# TurquoiseBicuspid.net
KiCad netlist of a schematic drawn in EAGLE
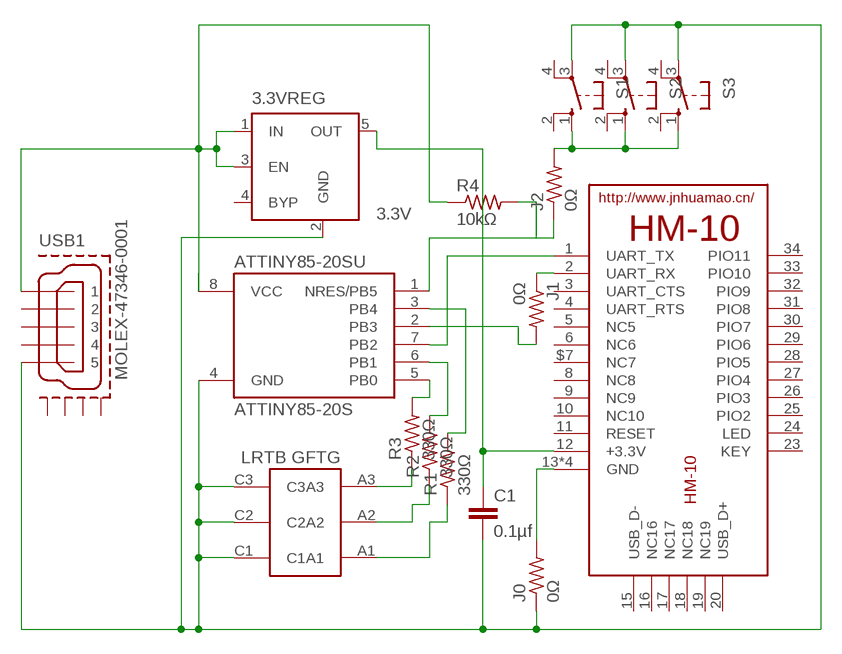
[diagram p0: schematic, sheet 1]

(export (version "E")
  (design (tool "Eeschema 10.0.6"))
  (components
    (comp (ref "3.3VREG")
      (value "3.3V")
      (footprint "eagle-import:SOT23-5")
      (libsource (lib "eagle-import") (part "MIC5219XX"))
    )
    (comp (ref "ATTINY85-20SU")
      (value "ATTINY85-20S")
      (footprint "eagle-import:SOIC8_EIAJ_208MIL")
      (libsource (lib "eagle-import") (part "ATTINY85S-20"))
    )
    (comp (ref "C1")
      (value "0.1µf")
      (footprint "eagle-import:C1206")
      (libsource (lib "eagle-import") (part "C-EUC1206"))
    )
    (comp (ref "HM-10")
      (value "HM-10-BOARD")
      (footprint "eagle-import:26.9X13X2.2_BOARD")
      (libsource (lib "eagle-import") (part "HM-10-BOARD"))
    )
    (comp (ref "J0")
      (value "0Ω")
      (footprint "eagle-import:R1206")
      (libsource (lib "eagle-import") (part "R-US_R1206"))
    )
    (comp (ref "J1")
      (value "0Ω")
      (footprint "eagle-import:R1206")
      (libsource (lib "eagle-import") (part "R-US_R1206"))
    )
    (comp (ref "J2")
      (value "0Ω")
      (footprint "eagle-import:R1206")
      (libsource (lib "eagle-import") (part "R-US_R1206"))
    )
    (comp (ref "R1")
      (value "330Ω")
      (footprint "eagle-import:M1206")
      (libsource (lib "eagle-import") (part "R-US_M1206"))
    )
    (comp (ref "R2")
      (value "330Ω")
      (footprint "eagle-import:M1206")
      (libsource (lib "eagle-import") (part "R-US_M1206"))
    )
    (comp (ref "R3")
      (value "330Ω")
      (footprint "eagle-import:M1206")
      (libsource (lib "eagle-import") (part "R-US_M1206"))
    )
    (comp (ref "R4")
      (value "10kΩ")
      (footprint "eagle-import:R1206")
      (libsource (lib "eagle-import") (part "R-US_R1206"))
    )
    (comp (ref "S1")
      (value "10-XX")
      (footprint "eagle-import:B3F-10XX")
      (fields (field (name "MPN") "B3F-1000"))
      (libsource (lib "eagle-import") (part "10-XX"))
    )
    (comp (ref "S2")
      (value "10-XX")
      (footprint "eagle-import:B3F-10XX")
      (fields (field (name "MPN") "B3F-1000"))
      (libsource (lib "eagle-import") (part "10-XX"))
    )
    (comp (ref "S3")
      (value "10-XX")
      (footprint "eagle-import:B3F-10XX")
      (fields (field (name "MPN") "B3F-1000"))
      (libsource (lib "eagle-import") (part "10-XX"))
    )
    (comp (ref "U$1")
      (value "LRTB_GFTG")
      (footprint "eagle-import:LRTB_GFTG")
      (libsource (lib "eagle-import") (part "LRTB_GFTG"))
    )
    (comp (ref "USB1")
      (value "MOLEX-47346-0001")
      (footprint "eagle-import:MOLEX-47364-0001")
      (libsource (lib "eagle-import") (part "MOLEX-47346-0001"))
    )
  )
  (nets
    (net (code "1") (name "/5V") (class "Default")
      (node (ref "3.3VREG") (pin "1") (pinfunction "IN_1") (pintype "input"))
      (node (ref "3.3VREG") (pin "3") (pinfunction "EN_3") (pintype "input"))
      (node (ref "ATTINY85-20SU") (pin "8") (pinfunction "VCC_8") (pintype "power_in"))
      (node (ref "R4") (pin "1") (pinfunction "1_1") (pintype "passive"))
      (node (ref "USB1") (pin "1") (pinfunction "1_1") (pintype "input"))
    )
    (net (code "2") (name "/A1") (class "Default")
      (node (ref "ATTINY85-20SU") (pin "3") (pinfunction "PB4_3") (pintype "bidirectional"))
      (node (ref "R1") (pin "1") (pinfunction "1_1") (pintype "passive"))
      (node (ref "R1") (pin "2") (pinfunction "2_2") (pintype "passive"))
      (node (ref "U$1") (pin "A1") (pinfunction "A1_A1") (pintype "bidirectional"))
    )
    (net (code "3") (name "/A2") (class "Default")
      (node (ref "ATTINY85-20SU") (pin "6") (pinfunction "PB1_6") (pintype "bidirectional"))
      (node (ref "R2") (pin "1") (pinfunction "1_1") (pintype "passive"))
      (node (ref "R2") (pin "2") (pinfunction "2_2") (pintype "passive"))
      (node (ref "U$1") (pin "A2") (pinfunction "A2_A2") (pintype "bidirectional"))
    )
    (net (code "4") (name "/A3") (class "Default")
      (node (ref "ATTINY85-20SU") (pin "5") (pinfunction "PB0_5") (pintype "bidirectional"))
      (node (ref "R3") (pin "1") (pinfunction "1_1") (pintype "passive"))
      (node (ref "R3") (pin "2") (pinfunction "2_2") (pintype "passive"))
      (node (ref "U$1") (pin "A3") (pinfunction "A3_A3") (pintype "bidirectional"))
    )
    (net (code "5") (name "/BT_RX") (class "Default")
      (node (ref "ATTINY85-20SU") (pin "2") (pinfunction "PB3_2") (pintype "bidirectional"))
      (node (ref "HM-10") (pin "2") (pinfunction "UART_RX_2") (pintype "bidirectional"))
      (node (ref "J1") (pin "1") (pinfunction "1_1") (pintype "passive"))
      (node (ref "J1") (pin "2") (pinfunction "2_2") (pintype "passive"))
    )
    (net (code "6") (name "/RESET") (class "Default")
      (node (ref "ATTINY85-20SU") (pin "1") (pinfunction "NRES/PB5_1") (pintype "bidirectional"))
      (node (ref "J2") (pin "1") (pinfunction "1_1") (pintype "passive"))
      (node (ref "J2") (pin "2") (pinfunction "2_2") (pintype "passive"))
      (node (ref "R4") (pin "2") (pinfunction "2_2") (pintype "passive"))
      (node (ref "S1") (pin "1") (pinfunction "S_1") (pintype "passive"))
      (node (ref "S2") (pin "1") (pinfunction "S_1") (pintype "passive"))
      (node (ref "S3") (pin "1") (pinfunction "S_1") (pintype "passive"))
    )
    (net (code "7") (name "Net-(3.3VREG-GND)") (class "Default")
      (node (ref "3.3VREG") (pin "2") (pinfunction "GND_2") (pintype "power_in"))
      (node (ref "ATTINY85-20SU") (pin "4") (pinfunction "GND_4") (pintype "power_in"))
      (node (ref "C1") (pin "2") (pinfunction "2_2") (pintype "passive"))
      (node (ref "J0") (pin "1") (pinfunction "1_1") (pintype "passive"))
      (node (ref "S1") (pin "3") (pinfunction "P_3") (pintype "passive"))
      (node (ref "S2") (pin "3") (pinfunction "P_3") (pintype "passive"))
      (node (ref "S3") (pin "3") (pinfunction "P_3") (pintype "passive"))
      (node (ref "U$1") (pin "C1") (pinfunction "C1_C1") (pintype "bidirectional"))
      (node (ref "U$1") (pin "C2") (pinfunction "C2_C2") (pintype "bidirectional"))
      (node (ref "U$1") (pin "C3") (pinfunction "C3_C3") (pintype "bidirectional"))
      (node (ref "USB1") (pin "5") (pinfunction "5_5") (pintype "input"))
    )
    (net (code "8") (name "Net-(3.3VREG-OUT)") (class "Default")
      (node (ref "3.3VREG") (pin "5") (pinfunction "OUT_5") (pintype "output"))
      (node (ref "C1") (pin "1") (pinfunction "1_1") (pintype "passive"))
      (node (ref "HM-10") (pin "12") (pinfunction "+3.3V_12") (pintype "bidirectional"))
    )
    (net (code "9") (name "Net-(ATTINY85-20SU-PB2)") (class "Default")
      (node (ref "ATTINY85-20SU") (pin "7") (pinfunction "PB2_7") (pintype "bidirectional"))
      (node (ref "HM-10") (pin "1") (pinfunction "UART_TX_1") (pintype "bidirectional"))
    )
    (net (code "10") (name "Net-(HM-10-GND-Pad13)") (class "Default")
      (node (ref "HM-10") (pin "13") (pinfunction "GND_13") (pintype "bidirectional"))
      (node (ref "HM-10") (pin "14") (pinfunction "GND_14") (pintype "bidirectional"))
      (node (ref "HM-10") (pin "21") (pinfunction "GND_21") (pintype "bidirectional"))
      (node (ref "HM-10") (pin "22") (pinfunction "GND_22") (pintype "bidirectional"))
      (node (ref "J0") (pin "2") (pinfunction "2_2") (pintype "passive"))
    )
    (net (code "11") (name "unconnected-(3.3VREG-BYP-Pad4)") (class "Default")
      (node (ref "3.3VREG") (pin "4") (pinfunction "BYP_4") (pintype "passive"))
    )
    (net (code "12") (name "unconnected-(HM-10-KEY-Pad23)") (class "Default")
      (node (ref "HM-10") (pin "23") (pinfunction "KEY_23") (pintype "bidirectional"))
    )
    (net (code "13") (name "unconnected-(HM-10-LED-Pad24)") (class "Default")
      (node (ref "HM-10") (pin "24") (pinfunction "LED_24") (pintype "bidirectional"))
    )
    (net (code "14") (name "unconnected-(HM-10-NC5-Pad5)") (class "Default")
      (node (ref "HM-10") (pin "5") (pinfunction "NC5_5") (pintype "bidirectional"))
    )
    (net (code "15") (name "unconnected-(HM-10-NC6-Pad6)") (class "Default")
      (node (ref "HM-10") (pin "6") (pinfunction "NC6_6") (pintype "bidirectional"))
    )
    (net (code "16") (name "unconnected-(HM-10-NC7-Pad$7)") (class "Default")
      (node (ref "HM-10") (pin "$7") (pinfunction "NC7_$7") (pintype "bidirectional"))
    )
    (net (code "17") (name "unconnected-(HM-10-NC8-Pad8)") (class "Default")
      (node (ref "HM-10") (pin "8") (pinfunction "NC8_8") (pintype "bidirectional"))
    )
    (net (code "18") (name "unconnected-(HM-10-NC9-Pad9)") (class "Default")
      (node (ref "HM-10") (pin "9") (pinfunction "NC9_9") (pintype "bidirectional"))
    )
    (net (code "19") (name "unconnected-(HM-10-NC10-Pad10)") (class "Default")
      (node (ref "HM-10") (pin "10") (pinfunction "NC10_10") (pintype "bidirectional"))
    )
    (net (code "20") (name "unconnected-(HM-10-NC16-Pad16)") (class "Default")
      (node (ref "HM-10") (pin "16") (pinfunction "NC16_16") (pintype "bidirectional"))
    )
    (net (code "21") (name "unconnected-(HM-10-NC17-Pad17)") (class "Default")
      (node (ref "HM-10") (pin "17") (pinfunction "NC17_17") (pintype "bidirectional"))
    )
    (net (code "22") (name "unconnected-(HM-10-NC18-Pad18)") (class "Default")
      (node (ref "HM-10") (pin "18") (pinfunction "NC18_18") (pintype "bidirectional"))
    )
    (net (code "23") (name "unconnected-(HM-10-NC19-Pad19)") (class "Default")
      (node (ref "HM-10") (pin "19") (pinfunction "NC19_19") (pintype "bidirectional"))
    )
    (net (code "24") (name "unconnected-(HM-10-PIO2-Pad25)") (class "Default")
      (node (ref "HM-10") (pin "25") (pinfunction "PIO2_25") (pintype "bidirectional"))
    )
    (net (code "25") (name "unconnected-(HM-10-PIO3-Pad26)") (class "Default")
      (node (ref "HM-10") (pin "26") (pinfunction "PIO3_26") (pintype "bidirectional"))
    )
    (net (code "26") (name "unconnected-(HM-10-PIO4-Pad27)") (class "Default")
      (node (ref "HM-10") (pin "27") (pinfunction "PIO4_27") (pintype "bidirectional"))
    )
    (net (code "27") (name "unconnected-(HM-10-PIO5-Pad28)") (class "Default")
      (node (ref "HM-10") (pin "28") (pinfunction "PIO5_28") (pintype "bidirectional"))
    )
    (net (code "28") (name "unconnected-(HM-10-PIO6-Pad29)") (class "Default")
      (node (ref "HM-10") (pin "29") (pinfunction "PIO6_29") (pintype "bidirectional"))
    )
    (net (code "29") (name "unconnected-(HM-10-PIO7-Pad30)") (class "Default")
      (node (ref "HM-10") (pin "30") (pinfunction "PIO7_30") (pintype "bidirectional"))
    )
    (net (code "30") (name "unconnected-(HM-10-PIO8-Pad31)") (class "Default")
      (node (ref "HM-10") (pin "31") (pinfunction "PIO8_31") (pintype "bidirectional"))
    )
    (net (code "31") (name "unconnected-(HM-10-PIO9-Pad32)") (class "Default")
      (node (ref "HM-10") (pin "32") (pinfunction "PIO9_32") (pintype "bidirectional"))
    )
    (net (code "32") (name "unconnected-(HM-10-PIO10-Pad33)") (class "Default")
      (node (ref "HM-10") (pin "33") (pinfunction "PIO10_33") (pintype "bidirectional"))
    )
    (net (code "33") (name "unconnected-(HM-10-PIO11-Pad34)") (class "Default")
      (node (ref "HM-10") (pin "34") (pinfunction "PIO11_34") (pintype "bidirectional"))
    )
    (net (code "34") (name "unconnected-(HM-10-RESET-Pad11)") (class "Default")
      (node (ref "HM-10") (pin "11") (pinfunction "RESET_11") (pintype "bidirectional"))
    )
    (net (code "35") (name "unconnected-(HM-10-UART_CTS-Pad3)") (class "Default")
      (node (ref "HM-10") (pin "3") (pinfunction "UART_CTS_3") (pintype "bidirectional"))
    )
    (net (code "36") (name "unconnected-(HM-10-UART_RTS-Pad4)") (class "Default")
      (node (ref "HM-10") (pin "4") (pinfunction "UART_RTS_4") (pintype "bidirectional"))
    )
    (net (code "37") (name "unconnected-(HM-10-USB_D+-Pad20)") (class "Default")
      (node (ref "HM-10") (pin "20") (pinfunction "USB_D+_20") (pintype "bidirectional"))
    )
    (net (code "38") (name "unconnected-(HM-10-USB_D--Pad15)") (class "Default")
      (node (ref "HM-10") (pin "15") (pinfunction "USB_D-_15") (pintype "bidirectional"))
    )
    (net (code "39") (name "unconnected-(S1-P1-Pad4)") (class "Default")
      (node (ref "S1") (pin "4") (pinfunction "P1_4") (pintype "passive"))
    )
    (net (code "40") (name "unconnected-(S1-S1-Pad2)") (class "Default")
      (node (ref "S1") (pin "2") (pinfunction "S1_2") (pintype "passive"))
    )
    (net (code "41") (name "unconnected-(S2-P1-Pad4)") (class "Default")
      (node (ref "S2") (pin "4") (pinfunction "P1_4") (pintype "passive"))
    )
    (net (code "42") (name "unconnected-(S2-S1-Pad2)") (class "Default")
      (node (ref "S2") (pin "2") (pinfunction "S1_2") (pintype "passive"))
    )
    (net (code "43") (name "unconnected-(S3-P1-Pad4)") (class "Default")
      (node (ref "S3") (pin "4") (pinfunction "P1_4") (pintype "passive"))
    )
    (net (code "44") (name "unconnected-(S3-S1-Pad2)") (class "Default")
      (node (ref "S3") (pin "2") (pinfunction "S1_2") (pintype "passive"))
    )
    (net (code "45") (name "unconnected-(USB1-Pad2)") (class "Default")
      (node (ref "USB1") (pin "2") (pinfunction "2_2") (pintype "input"))
    )
    (net (code "46") (name "unconnected-(USB1-Pad3)") (class "Default")
      (node (ref "USB1") (pin "3") (pinfunction "3_3") (pintype "input"))
    )
    (net (code "47") (name "unconnected-(USB1-Pad4)") (class "Default")
      (node (ref "USB1") (pin "4") (pinfunction "4_4") (pintype "input"))
    )
    (net (code "48") (name "unconnected-(USB1-PadGND1)") (class "Default")
      (node (ref "USB1") (pin "GND1") (pinfunction "GND1_GND1") (pintype "bidirectional"))
    )
    (net (code "49") (name "unconnected-(USB1-PadGND2)") (class "Default")
      (node (ref "USB1") (pin "GND2") (pinfunction "GND2_GND2") (pintype "bidirectional"))
    )
    (net (code "50") (name "unconnected-(USB1-PadGND3)") (class "Default")
      (node (ref "USB1") (pin "GND3") (pinfunction "GND3_GND3") (pintype "bidirectional"))
    )
    (net (code "51") (name "unconnected-(USB1-PadGND4)") (class "Default")
      (node (ref "USB1") (pin "GND4") (pinfunction "GND4_GND4") (pintype "bidirectional"))
    )
  )
)
